# Nanofeed_V2.net
KiCad netlist of a schematic drawn in EAGLE
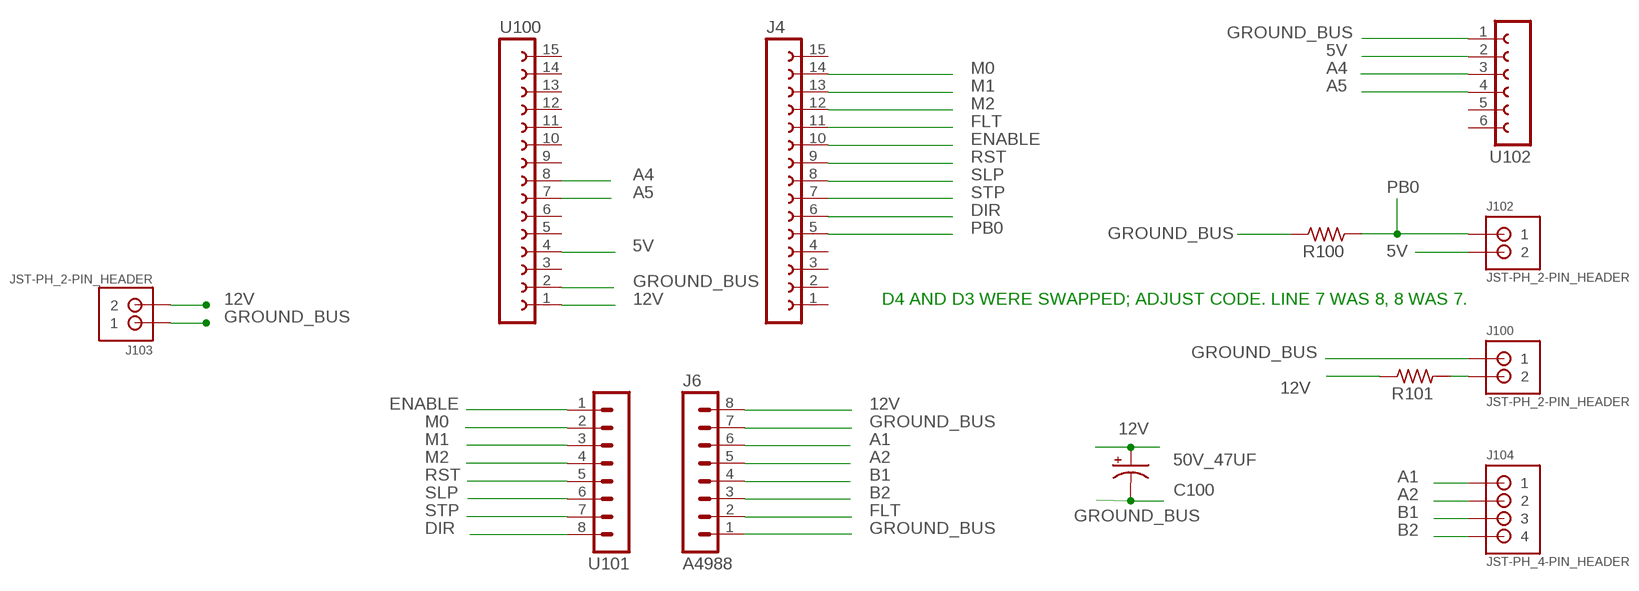
[diagram p0: schematic, sheet 1]

(export (version "E")
  (design (tool "Eeschema 10.0.6"))
  (components
    (comp (ref "C100")
      (value "50V_47UF")
      (footprint "eagle-import:PANASONIC_D")
      (libsource (lib "eagle-import") (part "47UF-POLAR-PANASONIC_D-50V-20%"))
    )
    (comp (ref "J4")
      (value "FE15-1")
      (footprint "eagle-import:FE15")
      (libsource (lib "eagle-import") (part "FE15-1"))
    )
    (comp (ref "J6")
      (value "A4988")
      (footprint "eagle-import:MA08-1")
      (libsource (lib "eagle-import") (part "MA08-1"))
    )
    (comp (ref "J100")
      (value "JST-PH_2-PIN_HEADER")
      (footprint "eagle-import:JST_B2B-PH_HEADER")
      (libsource (lib "eagle-import") (part "JST-PH_2-PIN_HEADER"))
    )
    (comp (ref "J102")
      (value "JST-PH_2-PIN_HEADER")
      (footprint "eagle-import:JST_B2B-PH_HEADER")
      (libsource (lib "eagle-import") (part "JST-PH_2-PIN_HEADER"))
    )
    (comp (ref "J103")
      (value "JST-PH_2-PIN_HEADER")
      (footprint "eagle-import:JST_B2B-PH_HEADER")
      (libsource (lib "eagle-import") (part "JST-PH_2-PIN_HEADER"))
    )
    (comp (ref "J104")
      (value "JST-PH_4-PIN_HEADER")
      (footprint "eagle-import:JST_B4B-PH_HEADER")
      (libsource (lib "eagle-import") (part "JST-PH_4-PIN_HEADER"))
    )
    (comp (ref "R100")
      (value "R_5025")
      (footprint "eagle-import:R5025")
      (libsource (lib "eagle-import") (part "R_5025"))
    )
    (comp (ref "R101")
      (value "R_5025")
      (footprint "eagle-import:R5025")
      (libsource (lib "eagle-import") (part "R_5025"))
    )
    (comp (ref "U100")
      (value "FE15-1")
      (footprint "eagle-import:FE15")
      (libsource (lib "eagle-import") (part "FE15-1"))
    )
    (comp (ref "U101")
      (value "MA08-1")
      (footprint "eagle-import:MA08-1")
      (libsource (lib "eagle-import") (part "MA08-1"))
    )
    (comp (ref "U102")
      (value "FE06-1")
      (footprint "eagle-import:FE06")
      (libsource (lib "eagle-import") (part "FE06-1"))
    )
  )
  (nets
    (net (code "1") (name "/5V") (class "Default")
      (node (ref "J102") (pin "P2") (pinfunction "2_P2") (pintype "bidirectional"))
      (node (ref "U100") (pin "4") (pinfunction "4_4") (pintype "passive"))
      (node (ref "U102") (pin "2") (pinfunction "2_2") (pintype "passive"))
    )
    (net (code "2") (name "/12V") (class "Default")
      (node (ref "C100") (pin "+") (pinfunction "+_+") (pintype "passive"))
      (node (ref "J103") (pin "P2") (pinfunction "2_P2") (pintype "bidirectional"))
      (node (ref "J6") (pin "8") (pinfunction "8_8") (pintype "passive"))
      (node (ref "R101") (pin "2") (pinfunction "2_2") (pintype "passive"))
      (node (ref "U100") (pin "1") (pinfunction "1_1") (pintype "passive"))
    )
    (net (code "3") (name "/A1") (class "Default")
      (node (ref "J104") (pin "P1") (pinfunction "1_P1") (pintype "bidirectional"))
      (node (ref "J6") (pin "6") (pinfunction "6_6") (pintype "passive"))
    )
    (net (code "4") (name "/A2") (class "Default")
      (node (ref "J104") (pin "P2") (pinfunction "2_P2") (pintype "bidirectional"))
      (node (ref "J6") (pin "5") (pinfunction "5_5") (pintype "passive"))
    )
    (net (code "5") (name "/A4") (class "Default")
      (node (ref "U100") (pin "8") (pinfunction "8_8") (pintype "passive"))
      (node (ref "U102") (pin "3") (pinfunction "3_3") (pintype "passive"))
    )
    (net (code "6") (name "/A5") (class "Default")
      (node (ref "U100") (pin "7") (pinfunction "7_7") (pintype "passive"))
      (node (ref "U102") (pin "4") (pinfunction "4_4") (pintype "passive"))
    )
    (net (code "7") (name "/B1") (class "Default")
      (node (ref "J104") (pin "P3") (pinfunction "3_P3") (pintype "bidirectional"))
      (node (ref "J6") (pin "4") (pinfunction "4_4") (pintype "passive"))
    )
    (net (code "8") (name "/B2") (class "Default")
      (node (ref "J104") (pin "P4") (pinfunction "4_P4") (pintype "bidirectional"))
      (node (ref "J6") (pin "3") (pinfunction "3_3") (pintype "passive"))
    )
    (net (code "9") (name "/DIR") (class "Default")
      (node (ref "J4") (pin "6") (pinfunction "6_6") (pintype "passive"))
      (node (ref "U101") (pin "8") (pinfunction "8_8") (pintype "passive"))
    )
    (net (code "10") (name "/ENABLE") (class "Default")
      (node (ref "J4") (pin "10") (pinfunction "10_10") (pintype "passive"))
      (node (ref "U101") (pin "1") (pinfunction "1_1") (pintype "passive"))
    )
    (net (code "11") (name "/FLT") (class "Default")
      (node (ref "J4") (pin "11") (pinfunction "11_11") (pintype "passive"))
      (node (ref "J6") (pin "2") (pinfunction "2_2") (pintype "passive"))
    )
    (net (code "12") (name "/GROUND_BUS") (class "Default")
      (node (ref "C100") (pin "-") (pinfunction "-_-") (pintype "passive"))
      (node (ref "J100") (pin "P1") (pinfunction "1_P1") (pintype "bidirectional"))
      (node (ref "J103") (pin "P1") (pinfunction "1_P1") (pintype "bidirectional"))
      (node (ref "J6") (pin "1") (pinfunction "1_1") (pintype "passive"))
      (node (ref "R100") (pin "2") (pinfunction "2_2") (pintype "passive"))
      (node (ref "U100") (pin "2") (pinfunction "2_2") (pintype "passive"))
      (node (ref "U102") (pin "1") (pinfunction "1_1") (pintype "passive"))
    )
    (net (code "13") (name "/M0") (class "Default")
      (node (ref "J4") (pin "14") (pinfunction "14_14") (pintype "passive"))
      (node (ref "U101") (pin "2") (pinfunction "2_2") (pintype "passive"))
    )
    (net (code "14") (name "/M1") (class "Default")
      (node (ref "J4") (pin "13") (pinfunction "13_13") (pintype "passive"))
      (node (ref "U101") (pin "3") (pinfunction "3_3") (pintype "passive"))
    )
    (net (code "15") (name "/M2") (class "Default")
      (node (ref "J4") (pin "12") (pinfunction "12_12") (pintype "passive"))
      (node (ref "U101") (pin "4") (pinfunction "4_4") (pintype "passive"))
    )
    (net (code "16") (name "/PB0") (class "Default")
      (node (ref "J102") (pin "P1") (pinfunction "1_P1") (pintype "bidirectional"))
      (node (ref "J4") (pin "5") (pinfunction "5_5") (pintype "passive"))
      (node (ref "R100") (pin "1") (pinfunction "1_1") (pintype "passive"))
    )
    (net (code "17") (name "/RST") (class "Default")
      (node (ref "J4") (pin "9") (pinfunction "9_9") (pintype "passive"))
      (node (ref "U101") (pin "5") (pinfunction "5_5") (pintype "passive"))
    )
    (net (code "18") (name "/SLP") (class "Default")
      (node (ref "J4") (pin "8") (pinfunction "8_8") (pintype "passive"))
      (node (ref "U101") (pin "6") (pinfunction "6_6") (pintype "passive"))
    )
    (net (code "19") (name "/STP") (class "Default")
      (node (ref "J4") (pin "7") (pinfunction "7_7") (pintype "passive"))
      (node (ref "U101") (pin "7") (pinfunction "7_7") (pintype "passive"))
    )
    (net (code "20") (name "Net-(J100-2)") (class "Default")
      (node (ref "J100") (pin "P2") (pinfunction "2_P2") (pintype "bidirectional"))
      (node (ref "R101") (pin "1") (pinfunction "1_1") (pintype "passive"))
    )
    (net (code "21") (name "unconnected-(J4-Pad1)") (class "Default")
      (node (ref "J4") (pin "1") (pinfunction "1_1") (pintype "passive"))
    )
    (net (code "22") (name "unconnected-(J4-Pad2)") (class "Default")
      (node (ref "J4") (pin "2") (pinfunction "2_2") (pintype "passive"))
    )
    (net (code "23") (name "unconnected-(J4-Pad3)") (class "Default")
      (node (ref "J4") (pin "3") (pinfunction "3_3") (pintype "passive"))
    )
    (net (code "24") (name "unconnected-(J4-Pad4)") (class "Default")
      (node (ref "J4") (pin "4") (pinfunction "4_4") (pintype "passive"))
    )
    (net (code "25") (name "unconnected-(J4-Pad15)") (class "Default")
      (node (ref "J4") (pin "15") (pinfunction "15_15") (pintype "passive"))
    )
    (net (code "26") (name "unconnected-(J6-Pad7)") (class "Default")
      (node (ref "J6") (pin "7") (pinfunction "7_7") (pintype "passive"))
    )
    (net (code "27") (name "unconnected-(U100-Pad3)") (class "Default")
      (node (ref "U100") (pin "3") (pinfunction "3_3") (pintype "passive"))
    )
    (net (code "28") (name "unconnected-(U100-Pad5)") (class "Default")
      (node (ref "U100") (pin "5") (pinfunction "5_5") (pintype "passive"))
    )
    (net (code "29") (name "unconnected-(U100-Pad6)") (class "Default")
      (node (ref "U100") (pin "6") (pinfunction "6_6") (pintype "passive"))
    )
    (net (code "30") (name "unconnected-(U100-Pad9)") (class "Default")
      (node (ref "U100") (pin "9") (pinfunction "9_9") (pintype "passive"))
    )
    (net (code "31") (name "unconnected-(U100-Pad10)") (class "Default")
      (node (ref "U100") (pin "10") (pinfunction "10_10") (pintype "passive"))
    )
    (net (code "32") (name "unconnected-(U100-Pad11)") (class "Default")
      (node (ref "U100") (pin "11") (pinfunction "11_11") (pintype "passive"))
    )
    (net (code "33") (name "unconnected-(U100-Pad12)") (class "Default")
      (node (ref "U100") (pin "12") (pinfunction "12_12") (pintype "passive"))
    )
    (net (code "34") (name "unconnected-(U100-Pad13)") (class "Default")
      (node (ref "U100") (pin "13") (pinfunction "13_13") (pintype "passive"))
    )
    (net (code "35") (name "unconnected-(U100-Pad14)") (class "Default")
      (node (ref "U100") (pin "14") (pinfunction "14_14") (pintype "passive"))
    )
    (net (code "36") (name "unconnected-(U100-Pad15)") (class "Default")
      (node (ref "U100") (pin "15") (pinfunction "15_15") (pintype "passive"))
    )
    (net (code "37") (name "unconnected-(U102-Pad5)") (class "Default")
      (node (ref "U102") (pin "5") (pinfunction "5_5") (pintype "passive"))
    )
    (net (code "38") (name "unconnected-(U102-Pad6)") (class "Default")
      (node (ref "U102") (pin "6") (pinfunction "6_6") (pintype "passive"))
    )
  )
)
